# Servo_Driver.net
KiCad netlist of a schematic drawn in Altium Designer
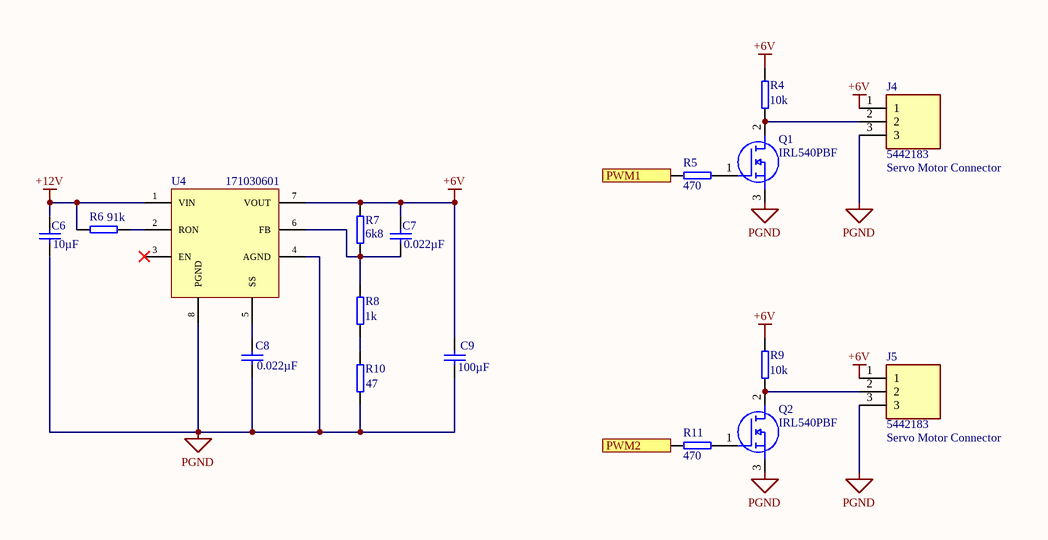
[diagram p0: Servo_Driver.SchDoc]

(export (version "E")
  (design (tool "Eeschema 10.0.6"))
  (components
    (comp (ref "C6")
      (value "10µF")
      (footprint "Capacitor 0603")
      (description "Capacitor")
      (libsource (lib "Schematic_Lib") (part "Capacitor 0603"))
    )
    (comp (ref "C7")
      (value "0.022µF")
      (footprint "Capacitor 0603")
      (description "Capacitor")
      (libsource (lib "Schematic_Lib") (part "Capacitor 0603"))
    )
    (comp (ref "C8")
      (value "0.022µF")
      (footprint "Capacitor 0603")
      (description "Capacitor")
      (libsource (lib "Schematic_Lib") (part "Capacitor 0603"))
    )
    (comp (ref "C9")
      (value "100µF")
      (footprint "Cap_1210")
      (description "Capacitor")
      (libsource (lib "Schematic_Lib") (part "Capacitor 1210"))
    )
    (comp (ref "J4")
      (value "5442183")
      (footprint "SamacSys:5442183")
      (description "Connector")
      (fields (field (name "MOUSER PART NUMBER") "651-5442183"))
      (libsource (lib "SamacSys") (part "5442183"))
    )
    (comp (ref "J5")
      (value "5442183")
      (footprint "SamacSys:5442183")
      (description "Connector")
      (fields (field (name "MOUSER PART NUMBER") "651-5442183"))
      (libsource (lib "SamacSys") (part "5442183"))
    )
    (comp (ref "Q1")
      (value "IRL540PBF")
      (footprint "TO-220-3")
      (description "MOSFET N-CH  100V HEXFET MOSFET")
      (fields (field (name "MOUSER PART NUMBER") "844-IRL540PBF"))
      (libsource (lib "Schematic_Lib") (part "IRL540PBF"))
    )
    (comp (ref "Q2")
      (value "IRL540PBF")
      (footprint "TO-220-3")
      (description "MOSFET N-CH  100V HEXFET MOSFET")
      (fields (field (name "MOUSER PART NUMBER") "844-IRL540PBF"))
      (libsource (lib "Schematic_Lib") (part "IRL540PBF"))
    )
    (comp (ref "R4")
      (value "10k")
      (footprint "Resistor 0603")
      (description "Resistor")
      (libsource (lib "Schematic_Lib") (part "Resistor 0603"))
    )
    (comp (ref "R5")
      (value "470")
      (footprint "Resistor 0603")
      (description "Resistor")
      (libsource (lib "Schematic_Lib") (part "Resistor 0603"))
    )
    (comp (ref "R6")
      (value "91k")
      (footprint "Resistor 0603")
      (description "Resistor")
      (libsource (lib "Schematic_Lib") (part "Resistor 0603"))
    )
    (comp (ref "R7")
      (value "6k8")
      (footprint "Resistor 0603")
      (description "Resistor")
      (libsource (lib "Schematic_Lib") (part "Resistor 0603"))
    )
    (comp (ref "R8")
      (value "1k")
      (footprint "Resistor 0603")
      (description "Resistor")
      (libsource (lib "Schematic_Lib") (part "Resistor 0603"))
    )
    (comp (ref "R9")
      (value "10k")
      (footprint "Resistor 0603")
      (description "Resistor")
      (libsource (lib "Schematic_Lib") (part "Resistor 0603"))
    )
    (comp (ref "R10")
      (value "47")
      (footprint "Resistor 0603")
      (description "Resistor")
      (libsource (lib "Schematic_Lib") (part "Resistor 0603"))
    )
    (comp (ref "R11")
      (value "470")
      (footprint "Resistor 0603")
      (description "Resistor")
      (libsource (lib "Schematic_Lib") (part "Resistor 0603"))
    )
    (comp (ref "U4")
      (value "171030601")
      (footprint "TO263-7EP")
      (description "MagI3C-VDRM Variable Step Down Regulator Module, TO263-7EP, 6-42Vin, 3Aout")
      (fields (field (name "MANUFACTURER") "Wurth Electronics"))
      (libsource (lib "Schematic_Lib") (part "CMP-533-000007-A.2"))
    )
  )
  (nets
    (net (code "1") (name "+6V") (class "Default")
      (node (ref "C7") (pin "1") (pinfunction "1_1") (pintype "passive"))
      (node (ref "C9") (pin "2") (pinfunction "2_2") (pintype "passive"))
      (node (ref "J4") (pin "1") (pinfunction "1_1") (pintype "passive"))
      (node (ref "J5") (pin "1") (pinfunction "1_1") (pintype "passive"))
      (node (ref "R4") (pin "1") (pintype "passive"))
      (node (ref "R7") (pin "1") (pintype "passive"))
      (node (ref "R9") (pin "1") (pintype "passive"))
      (node (ref "U4") (pin "7") (pinfunction "VOUT_7") (pintype "passive"))
    )
    (net (code "2") (name "+12V") (class "Default")
      (node (ref "C6") (pin "1") (pinfunction "1_1") (pintype "passive"))
      (node (ref "R6") (pin "1") (pintype "passive"))
      (node (ref "U4") (pin "1") (pinfunction "VIN_1") (pintype "passive"))
    )
    (net (code "3") (name "/PWM1") (class "Default") (node (ref "R5") (pin "1") (pintype "passive")))
    (net (code "4") (name "/PWM2") (class "Default") (node (ref "R11") (pin "1") (pintype "passive")))
    (net (code "5") (name "Net-(Q1-D)") (class "Default")
      (node (ref "J4") (pin "2") (pinfunction "2_2") (pintype "passive"))
      (node (ref "Q1") (pin "2") (pinfunction "D_2") (pintype "passive"))
      (node (ref "R4") (pin "2") (pintype "passive"))
    )
    (net (code "6") (name "Net-(Q1-G)") (class "Default")
      (node (ref "Q1") (pin "1") (pinfunction "G_1") (pintype "passive"))
      (node (ref "R5") (pin "2") (pintype "passive"))
    )
    (net (code "7") (name "Net-(Q2-D)") (class "Default")
      (node (ref "J5") (pin "2") (pinfunction "2_2") (pintype "passive"))
      (node (ref "Q2") (pin "2") (pinfunction "D_2") (pintype "passive"))
      (node (ref "R9") (pin "2") (pintype "passive"))
    )
    (net (code "8") (name "Net-(Q2-G)") (class "Default")
      (node (ref "Q2") (pin "1") (pinfunction "G_1") (pintype "passive"))
      (node (ref "R11") (pin "2") (pintype "passive"))
    )
    (net (code "9") (name "Net-(R10-Pad1)") (class "Default")
      (node (ref "R10") (pin "1") (pintype "passive"))
      (node (ref "R8") (pin "2") (pintype "passive"))
    )
    (net (code "10") (name "Net-(U4-FB)") (class "Default")
      (node (ref "C7") (pin "2") (pinfunction "2_2") (pintype "passive"))
      (node (ref "R7") (pin "2") (pintype "passive"))
      (node (ref "R8") (pin "1") (pintype "passive"))
      (node (ref "U4") (pin "6") (pinfunction "FB_6") (pintype "passive"))
    )
    (net (code "11") (name "Net-(U4-RON)") (class "Default")
      (node (ref "R6") (pin "2") (pintype "passive"))
      (node (ref "U4") (pin "2") (pinfunction "RON_2") (pintype "passive"))
    )
    (net (code "12") (name "Net-(U4-SS)") (class "Default")
      (node (ref "C8") (pin "2") (pinfunction "2_2") (pintype "passive"))
      (node (ref "U4") (pin "5") (pinfunction "SS_5") (pintype "passive"))
    )
    (net (code "13") (name "PGND") (class "Default")
      (node (ref "C6") (pin "2") (pinfunction "2_2") (pintype "passive"))
      (node (ref "C8") (pin "1") (pinfunction "1_1") (pintype "passive"))
      (node (ref "C9") (pin "1") (pinfunction "1_1") (pintype "passive"))
      (node (ref "J4") (pin "3") (pinfunction "3_3") (pintype "passive"))
      (node (ref "J5") (pin "3") (pinfunction "3_3") (pintype "passive"))
      (node (ref "Q1") (pin "3") (pinfunction "S_3") (pintype "passive"))
      (node (ref "Q2") (pin "3") (pinfunction "S_3") (pintype "passive"))
      (node (ref "R10") (pin "2") (pintype "passive"))
      (node (ref "U4") (pin "4") (pinfunction "AGND_4") (pintype "passive"))
      (node (ref "U4") (pin "8") (pinfunction "PGND_8") (pintype "passive"))
    )
    (net (code "14") (name "unconnected-(U4-EN-Pad3)") (class "Default")
      (node (ref "U4") (pin "3") (pinfunction "EN_3") (pintype "passive+no_connect"))
    )
  )
)
